# Binary_Counter_4060.net
KiCad netlist of a schematic drawn in EAGLE
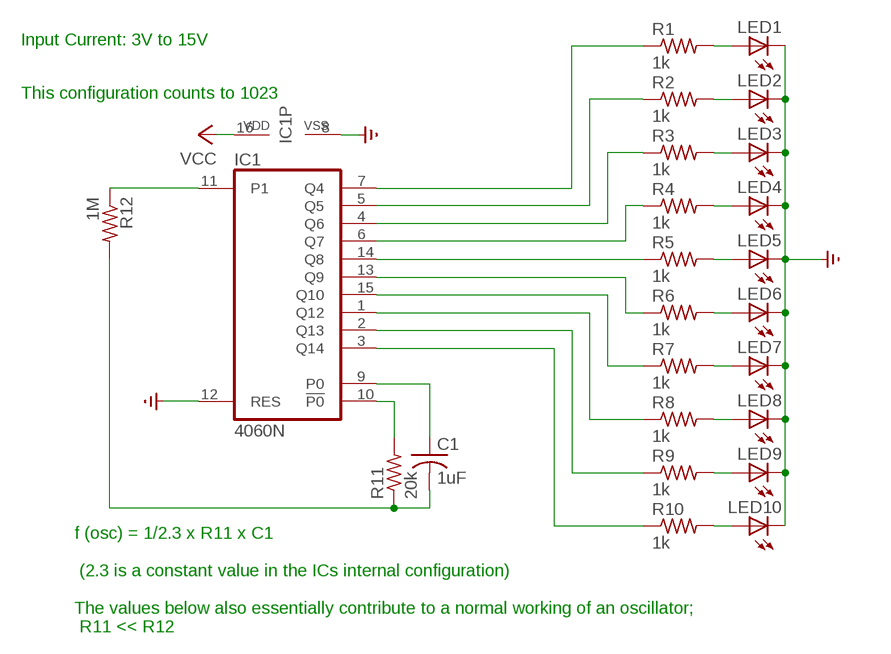
[diagram p0: schematic, sheet 1]

(export (version "E")
  (design (tool "Eeschema 10.0.6"))
  (components
    (comp (ref "C1")
      (value "1uF")
      (footprint "eagle-import:C050-030X075")
      (libsource (lib "eagle-import") (part "C-US050-030X075"))
    )
    (comp (ref "IC1")
      (value "4060N")
      (footprint "eagle-import:DIL16")
      (libsource (lib "eagle-import") (part "4060N"))
    )
    (comp (ref "LED1")
      (value "LED3MM")
      (footprint "eagle-import:LED3MM")
      (libsource (lib "eagle-import") (part "LED3MM"))
    )
    (comp (ref "LED2")
      (value "LED3MM")
      (footprint "eagle-import:LED3MM")
      (libsource (lib "eagle-import") (part "LED3MM"))
    )
    (comp (ref "LED3")
      (value "LED3MM")
      (footprint "eagle-import:LED3MM")
      (libsource (lib "eagle-import") (part "LED3MM"))
    )
    (comp (ref "LED4")
      (value "LED3MM")
      (footprint "eagle-import:LED3MM")
      (libsource (lib "eagle-import") (part "LED3MM"))
    )
    (comp (ref "LED5")
      (value "LED3MM")
      (footprint "eagle-import:LED3MM")
      (libsource (lib "eagle-import") (part "LED3MM"))
    )
    (comp (ref "LED6")
      (value "LED3MM")
      (footprint "eagle-import:LED3MM")
      (libsource (lib "eagle-import") (part "LED3MM"))
    )
    (comp (ref "LED7")
      (value "LED3MM")
      (footprint "eagle-import:LED3MM")
      (libsource (lib "eagle-import") (part "LED3MM"))
    )
    (comp (ref "LED8")
      (value "LED3MM")
      (footprint "eagle-import:LED3MM")
      (libsource (lib "eagle-import") (part "LED3MM"))
    )
    (comp (ref "LED9")
      (value "LED3MM")
      (footprint "eagle-import:LED3MM")
      (libsource (lib "eagle-import") (part "LED3MM"))
    )
    (comp (ref "LED10")
      (value "LED3MM")
      (footprint "eagle-import:LED3MM")
      (libsource (lib "eagle-import") (part "LED3MM"))
    )
    (comp (ref "R1")
      (value "1k")
      (footprint "eagle-import:0204_7")
      (libsource (lib "eagle-import") (part "R-US_0204/7"))
    )
    (comp (ref "R2")
      (value "1k")
      (footprint "eagle-import:0204_7")
      (libsource (lib "eagle-import") (part "R-US_0204/7"))
    )
    (comp (ref "R3")
      (value "1k")
      (footprint "eagle-import:0204_7")
      (libsource (lib "eagle-import") (part "R-US_0204/7"))
    )
    (comp (ref "R4")
      (value "1k")
      (footprint "eagle-import:0204_7")
      (libsource (lib "eagle-import") (part "R-US_0204/7"))
    )
    (comp (ref "R5")
      (value "1k")
      (footprint "eagle-import:0204_7")
      (libsource (lib "eagle-import") (part "R-US_0204/7"))
    )
    (comp (ref "R6")
      (value "1k")
      (footprint "eagle-import:0204_7")
      (libsource (lib "eagle-import") (part "R-US_0204/7"))
    )
    (comp (ref "R7")
      (value "1k")
      (footprint "eagle-import:0204_7")
      (libsource (lib "eagle-import") (part "R-US_0204/7"))
    )
    (comp (ref "R8")
      (value "1k")
      (footprint "eagle-import:0204_7")
      (libsource (lib "eagle-import") (part "R-US_0204/7"))
    )
    (comp (ref "R9")
      (value "1k")
      (footprint "eagle-import:0204_7")
      (libsource (lib "eagle-import") (part "R-US_0204/7"))
    )
    (comp (ref "R10")
      (value "1k")
      (footprint "eagle-import:0204_7")
      (libsource (lib "eagle-import") (part "R-US_0204/7"))
    )
    (comp (ref "R11")
      (value "20k")
      (footprint "eagle-import:0204_7")
      (libsource (lib "eagle-import") (part "R-US_0204/7"))
    )
    (comp (ref "R12")
      (value "1M")
      (footprint "eagle-import:0204_7")
      (libsource (lib "eagle-import") (part "R-US_0204/7"))
    )
  )
  (nets
    (net (code "1") (name "Net-(C1-Pad2)") (class "Default")
      (node (ref "C1") (pin "2") (pinfunction "2_2") (pintype "passive"))
      (node (ref "R11") (pin "1") (pinfunction "1_1") (pintype "passive"))
      (node (ref "R12") (pin "2") (pinfunction "2_2") (pintype "passive"))
    )
    (net (code "2") (name "Net-(IC1A-P0)") (class "Default")
      (node (ref "C1") (pin "1") (pinfunction "1_1") (pintype "passive"))
      (node (ref "IC1") (pin "9") (pinfunction "P0_9") (pintype "output"))
    )
    (net (code "3") (name "Net-(IC1A-P1)") (class "Default")
      (node (ref "IC1") (pin "11") (pinfunction "P1_11") (pintype "input"))
      (node (ref "R12") (pin "1") (pinfunction "1_1") (pintype "passive"))
    )
    (net (code "4") (name "Net-(IC1A-Q4)") (class "Default")
      (node (ref "IC1") (pin "7") (pinfunction "Q4_7") (pintype "output"))
      (node (ref "R1") (pin "1") (pinfunction "1_1") (pintype "passive"))
    )
    (net (code "5") (name "Net-(IC1A-Q5)") (class "Default")
      (node (ref "IC1") (pin "5") (pinfunction "Q5_5") (pintype "output"))
      (node (ref "R2") (pin "1") (pinfunction "1_1") (pintype "passive"))
    )
    (net (code "6") (name "Net-(IC1A-Q6)") (class "Default")
      (node (ref "IC1") (pin "4") (pinfunction "Q6_4") (pintype "output"))
      (node (ref "R3") (pin "1") (pinfunction "1_1") (pintype "passive"))
    )
    (net (code "7") (name "Net-(IC1A-Q7)") (class "Default")
      (node (ref "IC1") (pin "6") (pinfunction "Q7_6") (pintype "output"))
      (node (ref "R4") (pin "1") (pinfunction "1_1") (pintype "passive"))
    )
    (net (code "8") (name "Net-(IC1A-Q8)") (class "Default")
      (node (ref "IC1") (pin "14") (pinfunction "Q8_14") (pintype "output"))
      (node (ref "R5") (pin "1") (pinfunction "1_1") (pintype "passive"))
    )
    (net (code "9") (name "Net-(IC1A-Q9)") (class "Default")
      (node (ref "IC1") (pin "13") (pinfunction "Q9_13") (pintype "output"))
      (node (ref "R6") (pin "1") (pinfunction "1_1") (pintype "passive"))
    )
    (net (code "10") (name "Net-(IC1A-Q10)") (class "Default")
      (node (ref "IC1") (pin "15") (pinfunction "Q10_15") (pintype "output"))
      (node (ref "R7") (pin "1") (pinfunction "1_1") (pintype "passive"))
    )
    (net (code "11") (name "Net-(IC1A-Q12)") (class "Default")
      (node (ref "IC1") (pin "1") (pinfunction "Q12_1") (pintype "output"))
      (node (ref "R8") (pin "1") (pinfunction "1_1") (pintype "passive"))
    )
    (net (code "12") (name "Net-(IC1A-Q13)") (class "Default")
      (node (ref "IC1") (pin "2") (pinfunction "Q13_2") (pintype "output"))
      (node (ref "R9") (pin "1") (pinfunction "1_1") (pintype "passive"))
    )
    (net (code "13") (name "Net-(IC1A-Q14)") (class "Default")
      (node (ref "IC1") (pin "3") (pinfunction "Q14_3") (pintype "output"))
      (node (ref "R10") (pin "1") (pinfunction "1_1") (pintype "passive"))
    )
    (net (code "14") (name "Net-(IC1A-~{P0})") (class "Default")
      (node (ref "IC1") (pin "10") (pinfunction "~{P0}_10") (pintype "output"))
      (node (ref "R11") (pin "2") (pinfunction "2_2") (pintype "passive"))
    )
    (net (code "15") (name "Net-(LED1-PadA)") (class "Default")
      (node (ref "LED1") (pin "A") (pinfunction "A_A") (pintype "passive"))
      (node (ref "R1") (pin "2") (pinfunction "2_2") (pintype "passive"))
    )
    (net (code "16") (name "Net-(LED2-PadA)") (class "Default")
      (node (ref "LED2") (pin "A") (pinfunction "A_A") (pintype "passive"))
      (node (ref "R2") (pin "2") (pinfunction "2_2") (pintype "passive"))
    )
    (net (code "17") (name "Net-(LED3-PadA)") (class "Default")
      (node (ref "LED3") (pin "A") (pinfunction "A_A") (pintype "passive"))
      (node (ref "R3") (pin "2") (pinfunction "2_2") (pintype "passive"))
    )
    (net (code "18") (name "Net-(LED4-PadA)") (class "Default")
      (node (ref "LED4") (pin "A") (pinfunction "A_A") (pintype "passive"))
      (node (ref "R4") (pin "2") (pinfunction "2_2") (pintype "passive"))
    )
    (net (code "19") (name "Net-(LED5-PadA)") (class "Default")
      (node (ref "LED5") (pin "A") (pinfunction "A_A") (pintype "passive"))
      (node (ref "R5") (pin "2") (pinfunction "2_2") (pintype "passive"))
    )
    (net (code "20") (name "Net-(LED6-PadA)") (class "Default")
      (node (ref "LED6") (pin "A") (pinfunction "A_A") (pintype "passive"))
      (node (ref "R6") (pin "2") (pinfunction "2_2") (pintype "passive"))
    )
    (net (code "21") (name "Net-(LED7-PadA)") (class "Default")
      (node (ref "LED7") (pin "A") (pinfunction "A_A") (pintype "passive"))
      (node (ref "R7") (pin "2") (pinfunction "2_2") (pintype "passive"))
    )
    (net (code "22") (name "Net-(LED8-PadA)") (class "Default")
      (node (ref "LED8") (pin "A") (pinfunction "A_A") (pintype "passive"))
      (node (ref "R8") (pin "2") (pinfunction "2_2") (pintype "passive"))
    )
    (net (code "23") (name "Net-(LED9-PadA)") (class "Default")
      (node (ref "LED9") (pin "A") (pinfunction "A_A") (pintype "passive"))
      (node (ref "R9") (pin "2") (pinfunction "2_2") (pintype "passive"))
    )
    (net (code "24") (name "Net-(LED10-PadA)") (class "Default")
      (node (ref "LED10") (pin "A") (pinfunction "A_A") (pintype "passive"))
      (node (ref "R10") (pin "2") (pinfunction "2_2") (pintype "passive"))
    )
    (net (code "25") (name "SUPPLY0_GND_") (class "Default")
      (node (ref "IC1") (pin "12") (pinfunction "RES_12") (pintype "input"))
      (node (ref "IC1") (pin "8") (pinfunction "VSS_8") (pintype "power_in"))
      (node (ref "LED1") (pin "K") (pinfunction "C_K") (pintype "passive"))
      (node (ref "LED10") (pin "K") (pinfunction "C_K") (pintype "passive"))
      (node (ref "LED2") (pin "K") (pinfunction "C_K") (pintype "passive"))
      (node (ref "LED3") (pin "K") (pinfunction "C_K") (pintype "passive"))
      (node (ref "LED4") (pin "K") (pinfunction "C_K") (pintype "passive"))
      (node (ref "LED5") (pin "K") (pinfunction "C_K") (pintype "passive"))
      (node (ref "LED6") (pin "K") (pinfunction "C_K") (pintype "passive"))
      (node (ref "LED7") (pin "K") (pinfunction "C_K") (pintype "passive"))
      (node (ref "LED8") (pin "K") (pinfunction "C_K") (pintype "passive"))
      (node (ref "LED9") (pin "K") (pinfunction "C_K") (pintype "passive"))
    )
    (net (code "26") (name "VCC") (class "Default")
      (node (ref "IC1") (pin "16") (pinfunction "VDD_16") (pintype "power_in"))
    )
  )
)
